# LOGIC_AND_POWER.net
KiCad netlist of a schematic drawn in Altium Designer
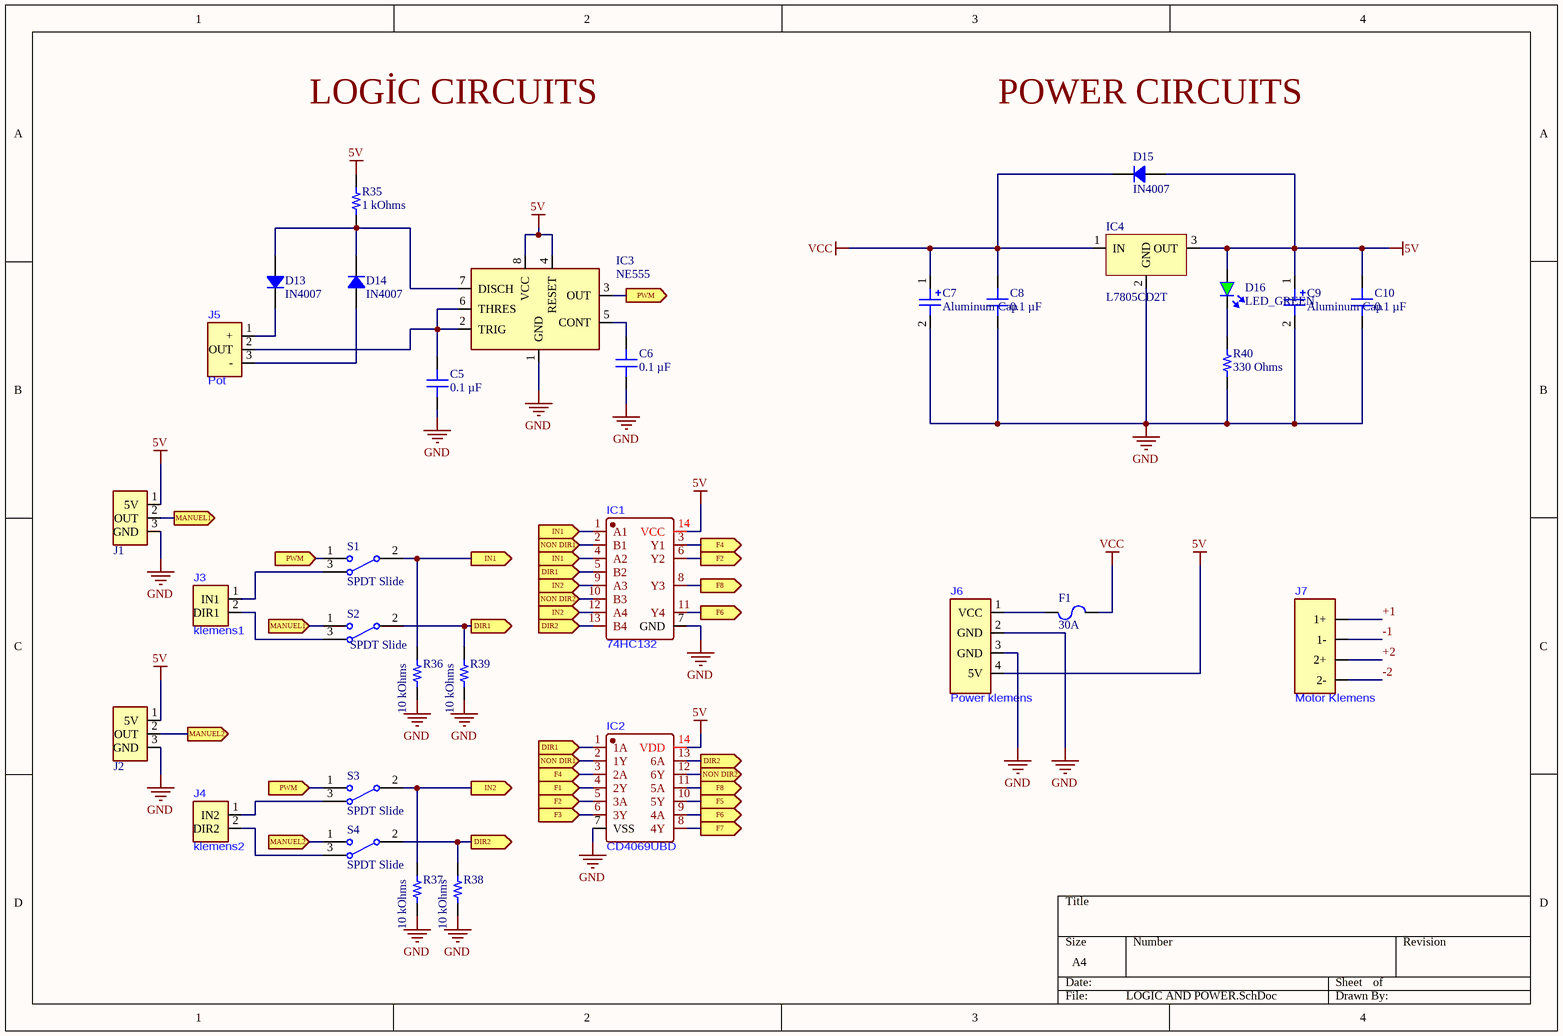
[diagram p0: LOGIC AND POWER.SchDoc]

(export (version "E")
  (design (tool "Eeschema 10.0.6"))
  (components
    (comp (ref "C5")
      (value "0.1 µF")
      (footprint "CAP 1210_3225 - 1MM")
      (description "1210 50VDC 100NF 10% X7R(2R1) AE")
      (fields (field (name "PART NUMBER") "1210Y0500104KST") (field (name "MANUFACTURER") "Knowles Syfer"))
      (libsource (lib "Celestial Altium Library - altium_library") (part "Capacitor"))
    )
    (comp (ref "C6")
      (value "0.1 µF")
      (footprint "CAP 1210_3225 - 1MM")
      (description "1210 50VDC 100NF 10% X7R(2R1) AE")
      (fields (field (name "PART NUMBER") "1210Y0500104KST") (field (name "MANUFACTURER") "Knowles Syfer"))
      (libsource (lib "Celestial Altium Library - altium_library") (part "Capacitor"))
    )
    (comp (ref "C7")
      (value "Aluminum Cap")
      (footprint "Aluminum Cap")
      (libsource (lib "HBRIDGE") (part "Aluminum Cap"))
    )
    (comp (ref "C8")
      (value "0.1 µF")
      (footprint "CAP 1210_3225 - 1MM")
      (description "1210 50VDC 100NF 10% X7R(2R1) AE")
      (fields (field (name "PART NUMBER") "1210Y0500104KST") (field (name "MANUFACTURER") "Knowles Syfer"))
      (libsource (lib "Celestial Altium Library - altium_library") (part "Capacitor"))
    )
    (comp (ref "C9")
      (value "Aluminum Cap")
      (footprint "Aluminum Cap")
      (libsource (lib "HBRIDGE") (part "Aluminum Cap"))
    )
    (comp (ref "C10")
      (value "0.1 µF")
      (footprint "CAP 1210_3225 - 1MM")
      (description "1210 50VDC 100NF 10% X7R(2R1) AE")
      (fields (field (name "PART NUMBER") "1210Y0500104KST") (field (name "MANUFACTURER") "Knowles Syfer"))
      (libsource (lib "Celestial Altium Library - altium_library") (part "Capacitor"))
    )
    (comp (ref "D13")
      (value "IN4007")
      (footprint "DO214AC SMA")
      (description "DIODE GEN PURP 50V 1A SMA")
      (fields (field (name "PART NUMBER") "RS1A") (field (name "MANUFACTURER") "ON Semiconductor"))
      (libsource (lib "Celestial Altium Library - altium_library") (part "Diode"))
    )
    (comp (ref "D14")
      (value "IN4007")
      (footprint "DO214AC SMA")
      (description "DIODE GEN PURP 50V 1A SMA")
      (fields (field (name "PART NUMBER") "RS1A") (field (name "MANUFACTURER") "ON Semiconductor"))
      (libsource (lib "Celestial Altium Library - altium_library") (part "Diode"))
    )
    (comp (ref "D15")
      (value "IN4007")
      (footprint "DO214AC SMA")
      (description "DIODE GEN PURP 50V 1A SMA")
      (fields (field (name "PART NUMBER") "RS1A") (field (name "MANUFACTURER") "ON Semiconductor"))
      (libsource (lib "Celestial Altium Library - altium_library") (part "Diode"))
    )
    (comp (ref "D16")
      (value "LED_GREEN")
      (footprint "LED_GREEN")
      (libsource (lib "HBRIDGE") (part "LED_GREEN"))
    )
    (comp (ref "F1")
      (value "30A")
      (footprint "FUSE 1206_3216 0.6MM")
      (description "FUSE BOARD MNT 2.5A 32VAC 63VDC")
      (fields (field (name "PART NUMBER") "3413.0120.22") (field (name "MANUFACTURER") "Schurter Inc."))
      (libsource (lib "Celestial Altium Library - altium_library") (part "MOUNTED FUSE"))
    )
    (comp (ref "IC1") (value "74HC132") (footprint "SOIC14") (libsource (lib "HBRIDGE") (part "74HC132")))
    (comp (ref "IC2") (value "CD4069UBD") (footprint "SOIC14") (libsource (lib "HBRIDGE") (part "CD4069UBD")))
    (comp (ref "IC3") (value "NE555") (footprint "NE5532-SOIC8") (libsource (lib "HBRIDGE") (part "NE555")))
    (comp (ref "IC4")
      (value "L7805CD2T")
      (footprint "L7805CD2T")
      (libsource (lib "HBRIDGE") (part "L7805CD2T"))
    )
    (comp (ref "J1")
      (value "Switch")
      (footprint "JST-XH 2.54 - duplicate")
      (libsource (lib "HBRIDGE_SCH_LIB") (part "switch"))
    )
    (comp (ref "J2")
      (value "Switch")
      (footprint "JST-XH 2.54 - duplicate")
      (libsource (lib "HBRIDGE_SCH_LIB") (part "switch"))
    )
    (comp (ref "J3") (value "klemens1") (footprint "Klemens") (libsource (lib "HBRIDGE") (part "klemens1")))
    (comp (ref "J4") (value "klemens2") (footprint "Klemens") (libsource (lib "HBRIDGE") (part "klemens2")))
    (comp (ref "J5") (value "Pot") (footprint "JST-XH 2.54") (libsource (lib "HBRIDGE") (part "Pot")))
    (comp (ref "J6")
      (value "Power klemens")
      (footprint "Power Klemens")
      (libsource (lib "HBRIDGE_SCH_LIB") (part "Power klemens"))
    )
    (comp (ref "J7")
      (value "Motor Klemens")
      (footprint "Power Klemens")
      (libsource (lib "HBRIDGE") (part "Motor Klemens"))
    )
    (comp (ref "R35")
      (value "1 kOhms")
      (footprint "RES 1206_3216")
      (description "RES 1K OHM 0.1% 1/8W 1206")
      (fields
        (field (name "PART NUMBER") "RNCS1206BKE1K00")
        (field (name "MANUFACTURER") "Stackpole Electronics Inc")
      )
      (libsource (lib "Celestial Altium Library - altium_library") (part "Resistor"))
    )
    (comp (ref "R36")
      (value "10 kOhms")
      (footprint "RES 1210_3225")
      (description "RES 10K OHM 1% 1/2W 1210")
      (fields
        (field (name "PART NUMBER") "RMCF1210FT10K0")
        (field (name "MANUFACTURER") "Stackpole Electronics Inc")
      )
      (libsource (lib "Celestial Altium Library - altium_library") (part "Resistor"))
    )
    (comp (ref "R37")
      (value "10 kOhms")
      (footprint "RES 1210_3225")
      (description "RES 10K OHM 1% 1/2W 1210")
      (fields
        (field (name "PART NUMBER") "RMCF1210FT10K0")
        (field (name "MANUFACTURER") "Stackpole Electronics Inc")
      )
      (libsource (lib "Celestial Altium Library - altium_library") (part "Resistor"))
    )
    (comp (ref "R38")
      (value "10 kOhms")
      (footprint "RES 1210_3225")
      (description "RES 10K OHM 1% 1/2W 1210")
      (fields
        (field (name "PART NUMBER") "RMCF1210FT10K0")
        (field (name "MANUFACTURER") "Stackpole Electronics Inc")
      )
      (libsource (lib "Celestial Altium Library - altium_library") (part "Resistor"))
    )
    (comp (ref "R39")
      (value "10 kOhms")
      (footprint "RES 1210_3225")
      (description "RES 10K OHM 1% 1/2W 1210")
      (fields
        (field (name "PART NUMBER") "RMCF1210FT10K0")
        (field (name "MANUFACTURER") "Stackpole Electronics Inc")
      )
      (libsource (lib "Celestial Altium Library - altium_library") (part "Resistor"))
    )
    (comp (ref "R40")
      (value "330 Ohms")
      (footprint "RES 1210_3225")
      (description "RES 330 OHM 1% 1/2W 1210")
      (fields
        (field (name "PART NUMBER") "RMCF1210FT330R")
        (field (name "MANUFACTURER") "Stackpole Electronics Inc")
      )
      (libsource (lib "Celestial Altium Library - altium_library") (part "Resistor"))
    )
    (comp (ref "S1") (value "SPDT Slide") (footprint "SPDT") (libsource (lib "HBRIDGE") (part "SPDT Slide")))
    (comp (ref "S2") (value "SPDT Slide") (footprint "SPDT") (libsource (lib "HBRIDGE") (part "SPDT Slide")))
    (comp (ref "S3") (value "SPDT Slide") (footprint "SPDT") (libsource (lib "HBRIDGE") (part "SPDT Slide")))
    (comp (ref "S4") (value "SPDT Slide") (footprint "SPDT") (libsource (lib "HBRIDGE") (part "SPDT Slide")))
  )
  (nets
    (net (code "1") (name "/+1") (class "Default")
      (node (ref "J7") (pin "1") (pinfunction "1+_1") (pintype "passive"))
    )
    (net (code "2") (name "/+2") (class "Default")
      (node (ref "J7") (pin "3") (pinfunction "2+_3") (pintype "passive"))
    )
    (net (code "3") (name "/-1") (class "Default")
      (node (ref "J7") (pin "2") (pinfunction "1-_2") (pintype "passive"))
    )
    (net (code "4") (name "/-2") (class "Default")
      (node (ref "J7") (pin "4") (pinfunction "2-_4") (pintype "passive"))
    )
    (net (code "5") (name "/DIR1") (class "Default")
      (node (ref "IC1") (pin "5") (pinfunction "B2_5") (pintype "passive"))
      (node (ref "IC2") (pin "1") (pinfunction "1A_1") (pintype "passive"))
      (node (ref "R39") (pin "2") (pinfunction "2_2") (pintype "passive"))
      (node (ref "S2") (pin "2") (pinfunction "0_2") (pintype "passive"))
    )
    (net (code "6") (name "/DIR2") (class "Default")
      (node (ref "IC1") (pin "13") (pinfunction "B4_13") (pintype "passive"))
      (node (ref "IC2") (pin "13") (pinfunction "6A_13") (pintype "passive"))
      (node (ref "R38") (pin "2") (pinfunction "2_2") (pintype "passive"))
      (node (ref "S4") (pin "2") (pinfunction "0_2") (pintype "passive"))
    )
    (net (code "7") (name "/F1") (class "Default")
      (node (ref "IC2") (pin "4") (pinfunction "2Y_4") (pintype "passive"))
    )
    (net (code "8") (name "/F2") (class "Default")
      (node (ref "IC1") (pin "6") (pinfunction "Y2_6") (pintype "passive"))
      (node (ref "IC2") (pin "5") (pinfunction "3A_5") (pintype "passive"))
    )
    (net (code "9") (name "/F3") (class "Default")
      (node (ref "IC2") (pin "6") (pinfunction "3Y_6") (pintype "passive"))
    )
    (net (code "10") (name "/F4") (class "Default")
      (node (ref "IC1") (pin "3") (pinfunction "Y1_3") (pintype "passive"))
      (node (ref "IC2") (pin "3") (pinfunction "2A_3") (pintype "passive"))
    )
    (net (code "11") (name "/F5") (class "Default")
      (node (ref "IC2") (pin "10") (pinfunction "5Y_10") (pintype "passive"))
    )
    (net (code "12") (name "/F6") (class "Default")
      (node (ref "IC1") (pin "11") (pinfunction "Y4_11") (pintype "passive"))
      (node (ref "IC2") (pin "9") (pinfunction "4A_9") (pintype "passive"))
    )
    (net (code "13") (name "/F7") (class "Default")
      (node (ref "IC2") (pin "8") (pinfunction "4Y_8") (pintype "passive"))
    )
    (net (code "14") (name "/F8") (class "Default")
      (node (ref "IC1") (pin "8") (pinfunction "Y3_8") (pintype "passive"))
      (node (ref "IC2") (pin "11") (pinfunction "5A_11") (pintype "passive"))
    )
    (net (code "15") (name "/IN1") (class "Default")
      (node (ref "IC1") (pin "1") (pinfunction "A1_1") (pintype "passive"))
      (node (ref "IC1") (pin "4") (pinfunction "A2_4") (pintype "passive"))
      (node (ref "R36") (pin "2") (pinfunction "2_2") (pintype "passive"))
      (node (ref "S1") (pin "2") (pinfunction "0_2") (pintype "passive"))
    )
    (net (code "16") (name "/IN2") (class "Default")
      (node (ref "IC1") (pin "12") (pinfunction "A4_12") (pintype "passive"))
      (node (ref "IC1") (pin "9") (pinfunction "A3_9") (pintype "passive"))
      (node (ref "R37") (pin "2") (pinfunction "2_2") (pintype "passive"))
      (node (ref "S3") (pin "2") (pinfunction "0_2") (pintype "passive"))
    )
    (net (code "18") (name "/MANUEL1") (class "Default")
      (node (ref "J1") (pin "2") (pinfunction "OUT_2") (pintype "passive"))
      (node (ref "S2") (pin "1") (pinfunction "PWM_1") (pintype "passive"))
    )
    (net (code "19") (name "/MANUEL2") (class "Default")
      (node (ref "J2") (pin "2") (pinfunction "OUT_2") (pintype "passive"))
      (node (ref "S4") (pin "1") (pinfunction "PWM_1") (pintype "passive"))
    )
    (net (code "20") (name "/NON DIR1") (class "Default")
      (node (ref "IC1") (pin "2") (pinfunction "B1_2") (pintype "passive"))
      (node (ref "IC2") (pin "2") (pinfunction "1Y_2") (pintype "passive"))
    )
    (net (code "21") (name "/NON DIR2") (class "Default")
      (node (ref "IC1") (pin "10") (pinfunction "B3_10") (pintype "passive"))
      (node (ref "IC2") (pin "12") (pinfunction "6Y_12") (pintype "passive"))
    )
    (net (code "23") (name "/PWM") (class "Default")
      (node (ref "IC3") (pin "3") (pinfunction "OUT_3") (pintype "passive"))
      (node (ref "S1") (pin "1") (pinfunction "PWM_1") (pintype "passive"))
      (node (ref "S3") (pin "1") (pinfunction "PWM_1") (pintype "passive"))
    )
    (net (code "24") (name "5V") (class "Default")
      (node (ref "C10") (pin "2") (pinfunction "2_2") (pintype "passive"))
      (node (ref "C9") (pin "1") (pinfunction "in_1") (pintype "passive"))
      (node (ref "D15") (pin "1") (pinfunction "1_1") (pintype "passive"))
      (node (ref "D16") (pin "1") (pinfunction "IN_1") (pintype "passive"))
      (node (ref "IC1") (pin "14") (pinfunction "VCC_14") (pintype "passive"))
      (node (ref "IC2") (pin "14") (pinfunction "VDD_14") (pintype "passive"))
      (node (ref "IC3") (pin "4") (pinfunction "RESET_4") (pintype "passive"))
      (node (ref "IC3") (pin "8") (pinfunction "VCC_8") (pintype "passive"))
      (node (ref "IC4") (pin "3") (pinfunction "OUT_3") (pintype "passive"))
      (node (ref "J1") (pin "1") (pinfunction "5V_1") (pintype "passive"))
      (node (ref "J2") (pin "1") (pinfunction "5V_1") (pintype "passive"))
      (node (ref "J6") (pin "4") (pinfunction "5V_4") (pintype "passive"))
      (node (ref "R35") (pin "1") (pinfunction "1_1") (pintype "passive"))
    )
    (net (code "25") (name "GND") (class "Default")
      (node (ref "C10") (pin "1") (pinfunction "1_1") (pintype "passive"))
      (node (ref "C5") (pin "1") (pinfunction "1_1") (pintype "passive"))
      (node (ref "C6") (pin "1") (pinfunction "1_1") (pintype "passive"))
      (node (ref "C7") (pin "2") (pinfunction "out_2") (pintype "passive"))
      (node (ref "C8") (pin "1") (pinfunction "1_1") (pintype "passive"))
      (node (ref "C9") (pin "2") (pinfunction "out_2") (pintype "passive"))
      (node (ref "IC1") (pin "7") (pinfunction "GND_7") (pintype "passive"))
      (node (ref "IC2") (pin "7") (pinfunction "VSS_7") (pintype "passive"))
      (node (ref "IC3") (pin "1") (pinfunction "GND_1") (pintype "passive"))
      (node (ref "IC4") (pin "2") (pinfunction "GND_2") (pintype "passive"))
      (node (ref "J1") (pin "3") (pinfunction "GND_3") (pintype "passive"))
      (node (ref "J2") (pin "3") (pinfunction "GND_3") (pintype "passive"))
      (node (ref "J6") (pin "2") (pinfunction "GND_2") (pintype "passive"))
      (node (ref "J6") (pin "3") (pinfunction "GND_3") (pintype "passive"))
      (node (ref "R36") (pin "1") (pinfunction "1_1") (pintype "passive"))
      (node (ref "R37") (pin "1") (pinfunction "1_1") (pintype "passive"))
      (node (ref "R38") (pin "1") (pinfunction "1_1") (pintype "passive"))
      (node (ref "R39") (pin "1") (pinfunction "1_1") (pintype "passive"))
      (node (ref "R40") (pin "1") (pinfunction "1_1") (pintype "passive"))
    )
    (net (code "26") (name "Net-(D16-OUT)") (class "Default")
      (node (ref "D16") (pin "2") (pinfunction "OUT_2") (pintype "passive"))
      (node (ref "R40") (pin "2") (pinfunction "2_2") (pintype "passive"))
    )
    (net (code "27") (name "Net-(IC3-CONT)") (class "Default")
      (node (ref "C6") (pin "2") (pinfunction "2_2") (pintype "passive"))
      (node (ref "IC3") (pin "5") (pinfunction "CONT_5") (pintype "passive"))
    )
    (net (code "28") (name "Net-(IC3-DISCH)") (class "Default")
      (node (ref "D13") (pin "1") (pinfunction "1_1") (pintype "passive"))
      (node (ref "D14") (pin "2") (pinfunction "2_2") (pintype "passive"))
      (node (ref "IC3") (pin "7") (pinfunction "DISCH_7") (pintype "passive"))
      (node (ref "R35") (pin "2") (pinfunction "2_2") (pintype "passive"))
    )
    (net (code "29") (name "Net-(IC3-THRES)") (class "Default")
      (node (ref "C5") (pin "2") (pinfunction "2_2") (pintype "passive"))
      (node (ref "IC3") (pin "2") (pinfunction "TRIG_2") (pintype "passive"))
      (node (ref "IC3") (pin "6") (pinfunction "THRES_6") (pintype "passive"))
      (node (ref "J5") (pin "2") (pinfunction "OUT_2") (pintype "passive"))
    )
    (net (code "30") (name "Net-(J3-DIR1)") (class "Default")
      (node (ref "J3") (pin "2") (pinfunction "DIR1_2") (pintype "passive"))
      (node (ref "S2") (pin "3") (pinfunction "MCU_3") (pintype "passive"))
    )
    (net (code "31") (name "Net-(J3-IN1)") (class "Default")
      (node (ref "J3") (pin "1") (pinfunction "IN1_1") (pintype "passive"))
      (node (ref "S1") (pin "3") (pinfunction "MCU_3") (pintype "passive"))
    )
    (net (code "32") (name "Net-(J4-DIR2)") (class "Default")
      (node (ref "J4") (pin "2") (pinfunction "DIR2_2") (pintype "passive"))
      (node (ref "S4") (pin "3") (pinfunction "MCU_3") (pintype "passive"))
    )
    (net (code "33") (name "Net-(J4-IN2)") (class "Default")
      (node (ref "J4") (pin "1") (pinfunction "IN2_1") (pintype "passive"))
      (node (ref "S3") (pin "3") (pinfunction "MCU_3") (pintype "passive"))
    )
    (net (code "34") (name "Net-(J5-+)") (class "Default")
      (node (ref "D13") (pin "2") (pinfunction "2_2") (pintype "passive"))
      (node (ref "J5") (pin "1") (pinfunction "+_1") (pintype "passive"))
    )
    (net (code "35") (name "Net-(J5--)") (class "Default")
      (node (ref "D14") (pin "1") (pinfunction "1_1") (pintype "passive"))
      (node (ref "J5") (pin "3") (pinfunction "-_3") (pintype "passive"))
    )
    (net (code "36") (name "Net-(J6-VCC)") (class "Default")
      (node (ref "F1") (pin "1") (pintype "passive"))
      (node (ref "J6") (pin "1") (pinfunction "VCC_1") (pintype "passive"))
    )
    (net (code "37") (name "VCC") (class "Default")
      (node (ref "C7") (pin "1") (pinfunction "in_1") (pintype "passive"))
      (node (ref "C8") (pin "2") (pinfunction "2_2") (pintype "passive"))
      (node (ref "D15") (pin "2") (pinfunction "2_2") (pintype "passive"))
      (node (ref "F1") (pin "2") (pintype "passive"))
      (node (ref "IC4") (pin "1") (pinfunction "IN_1") (pintype "passive"))
    )
  )
)
